# FY.net
KiCad netlist of a schematic drawn in EAGLE
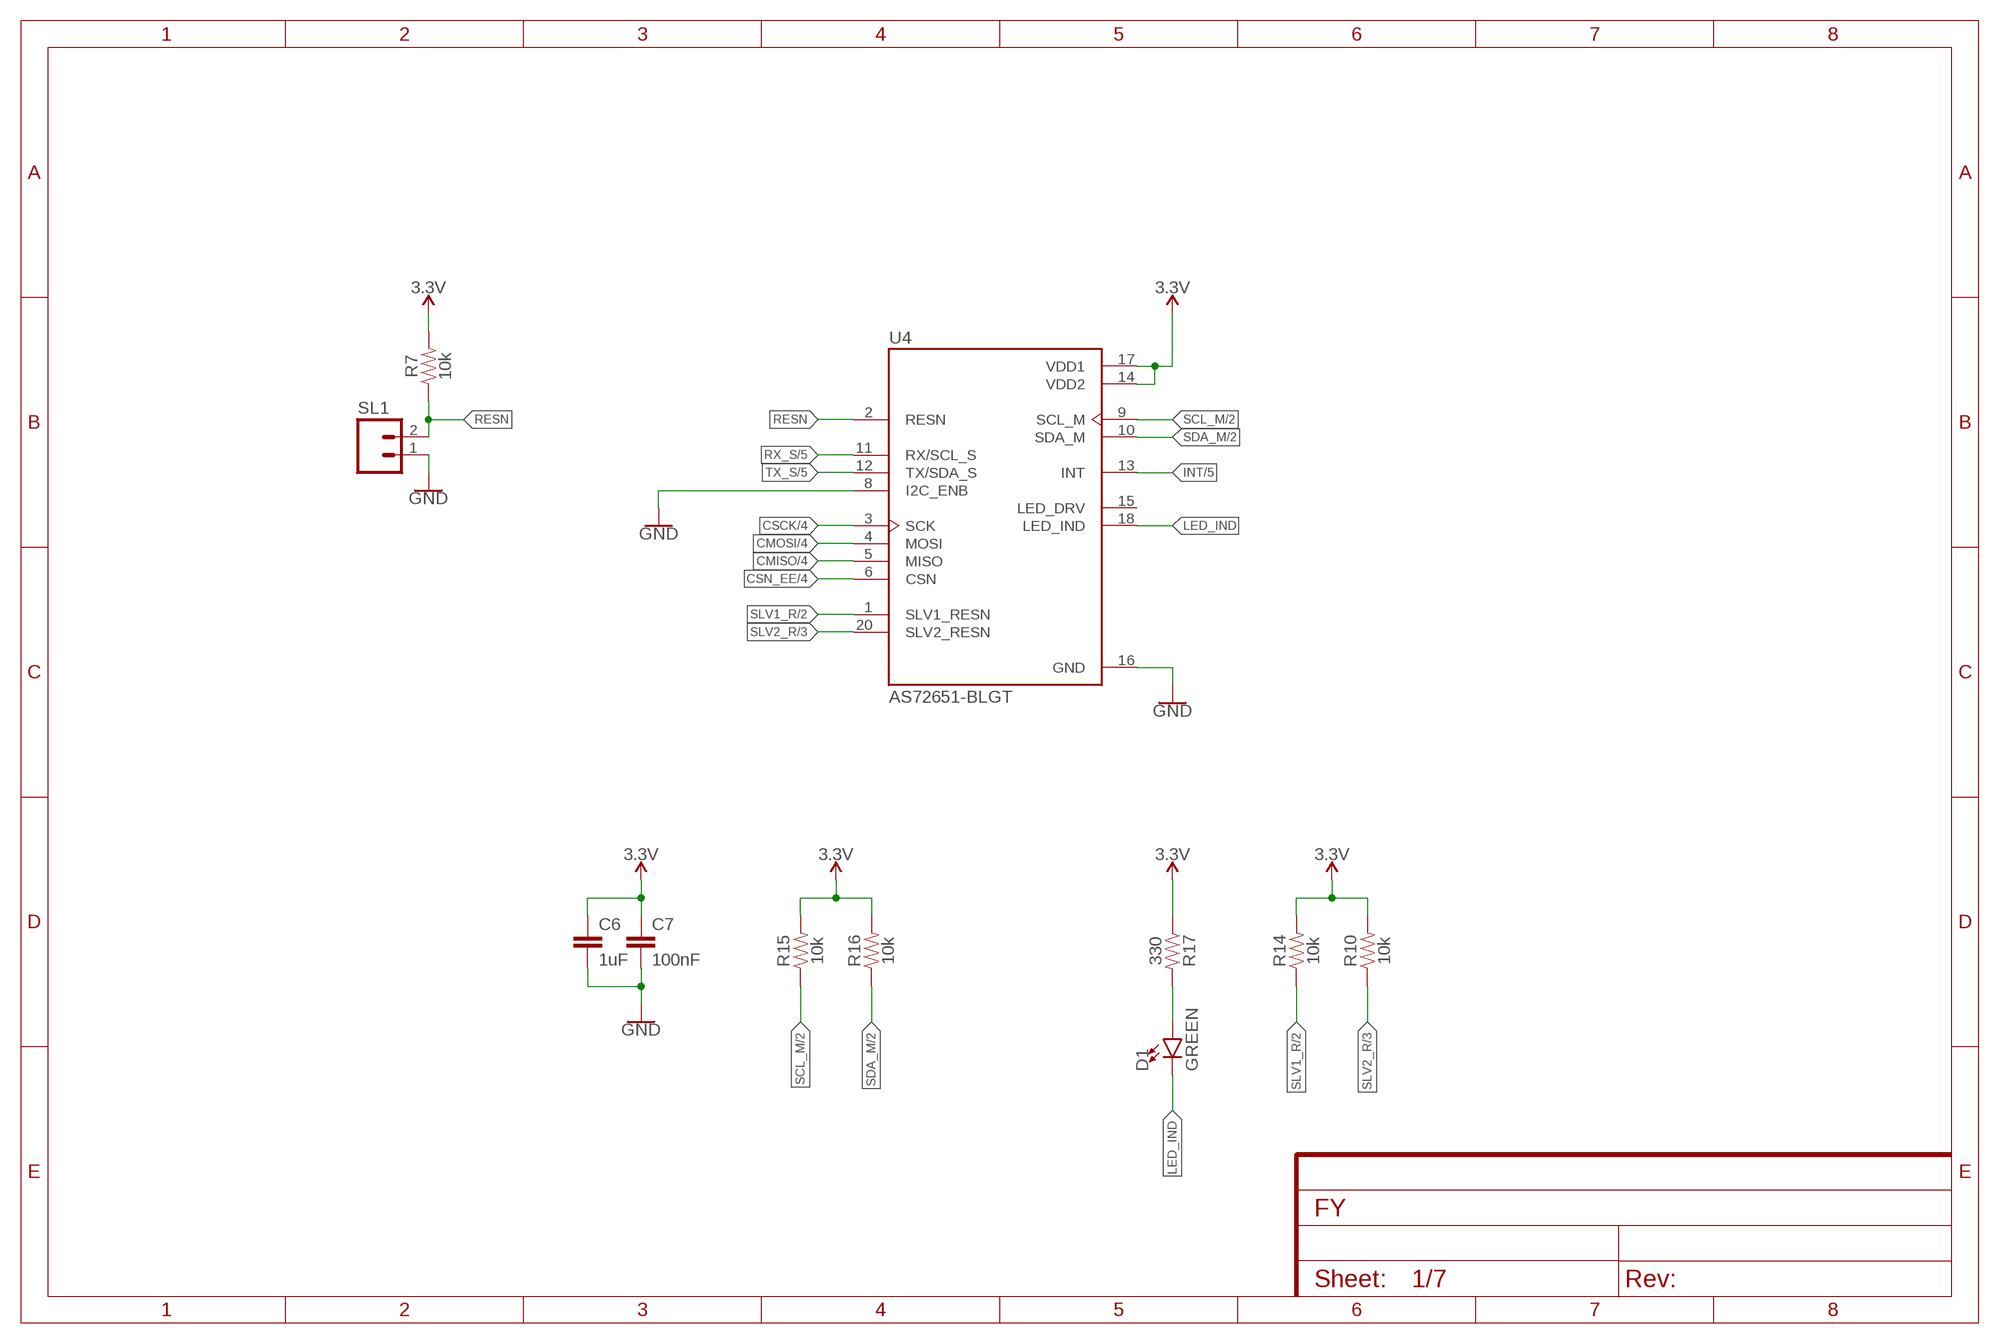
[diagram p0: schematic, sheet 1]
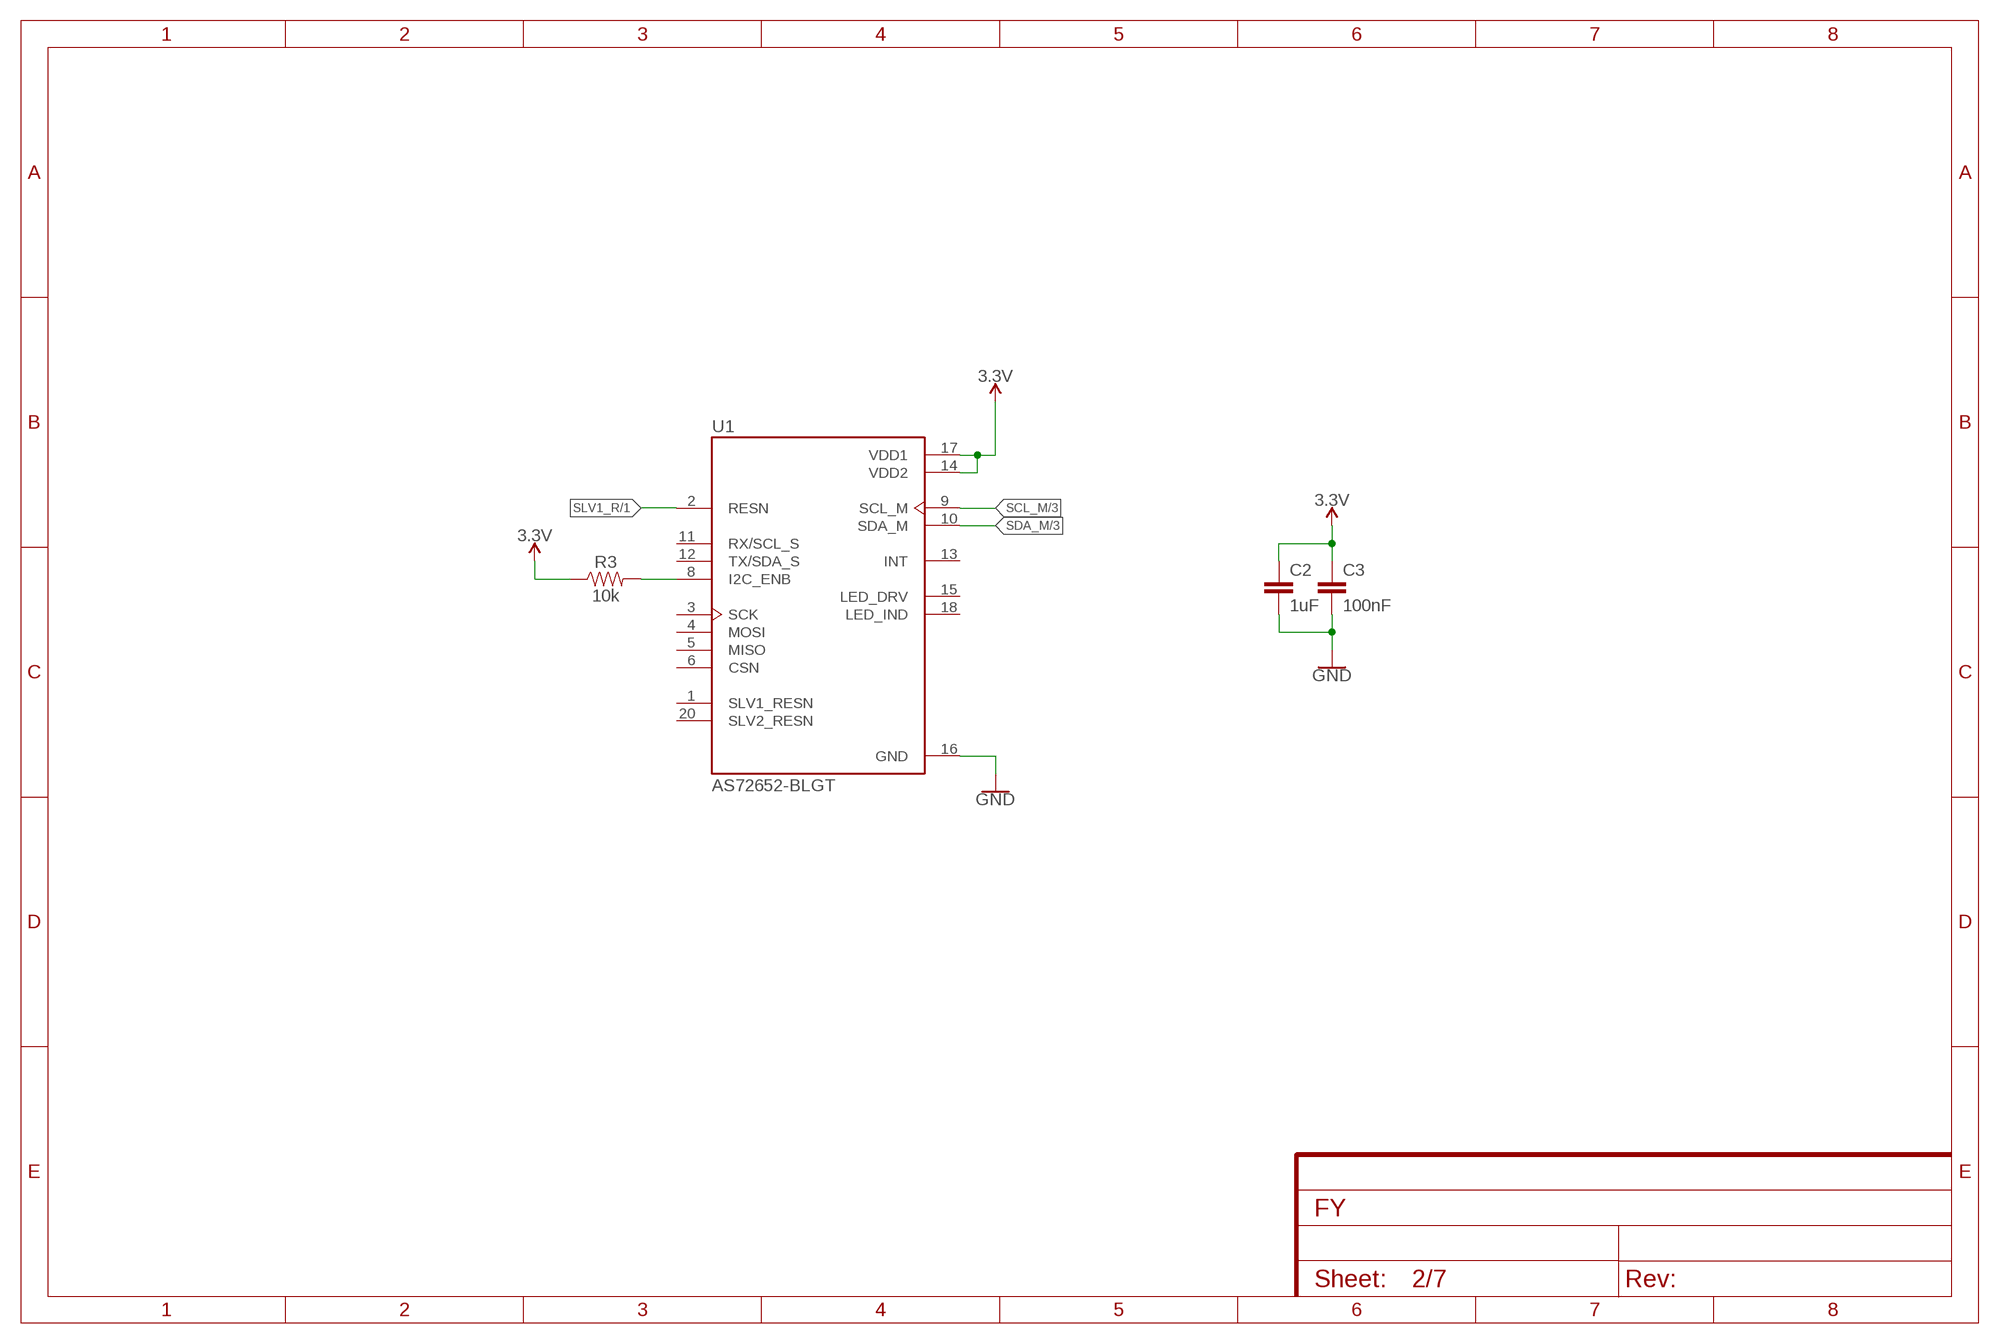
[diagram p1: schematic, sheet 2]
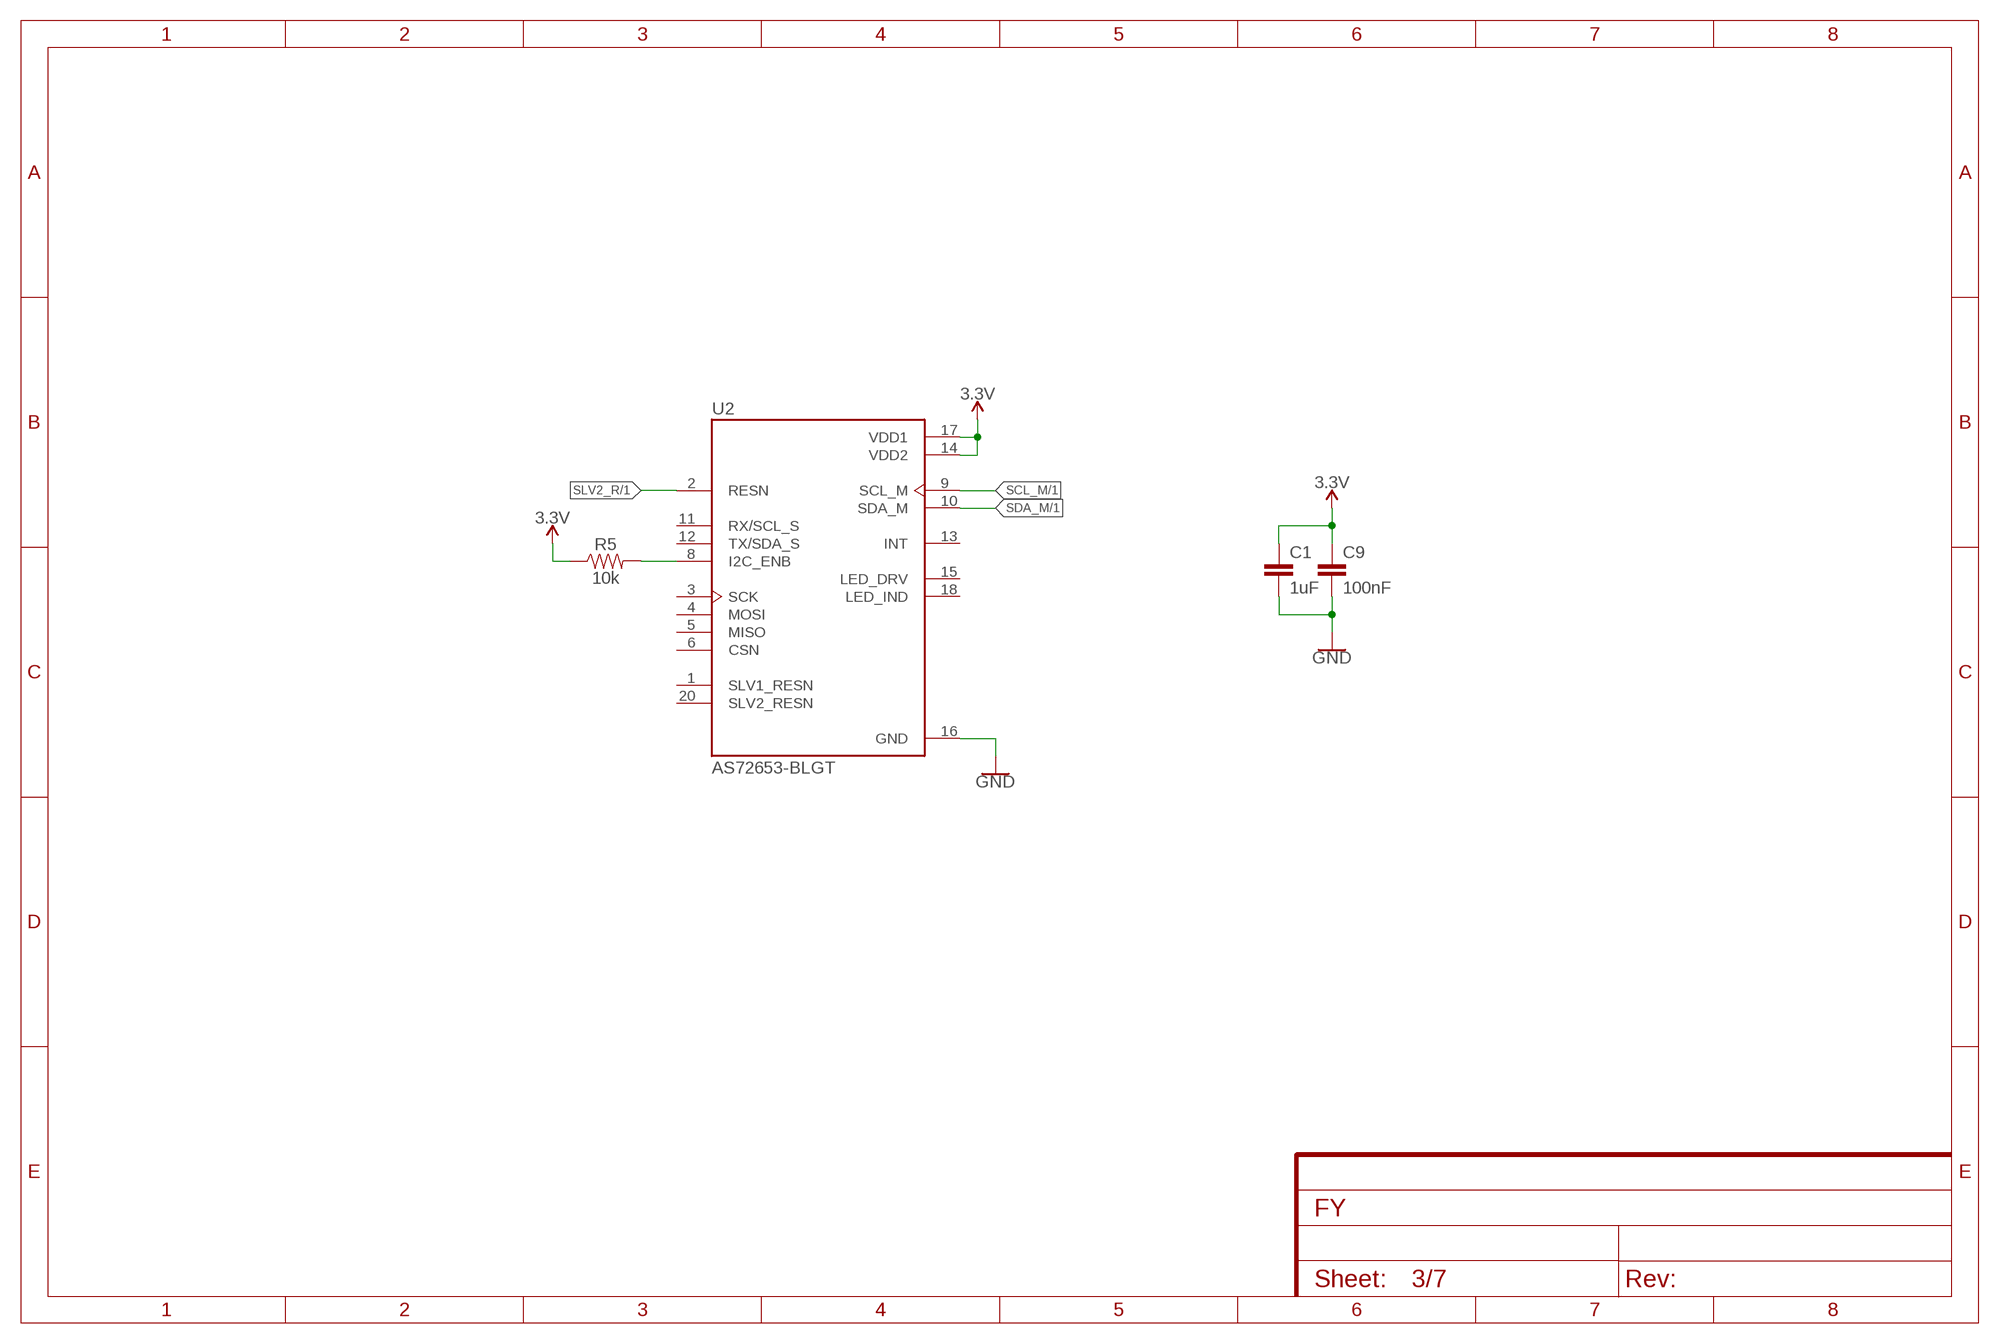
[diagram p2: schematic, sheet 3]
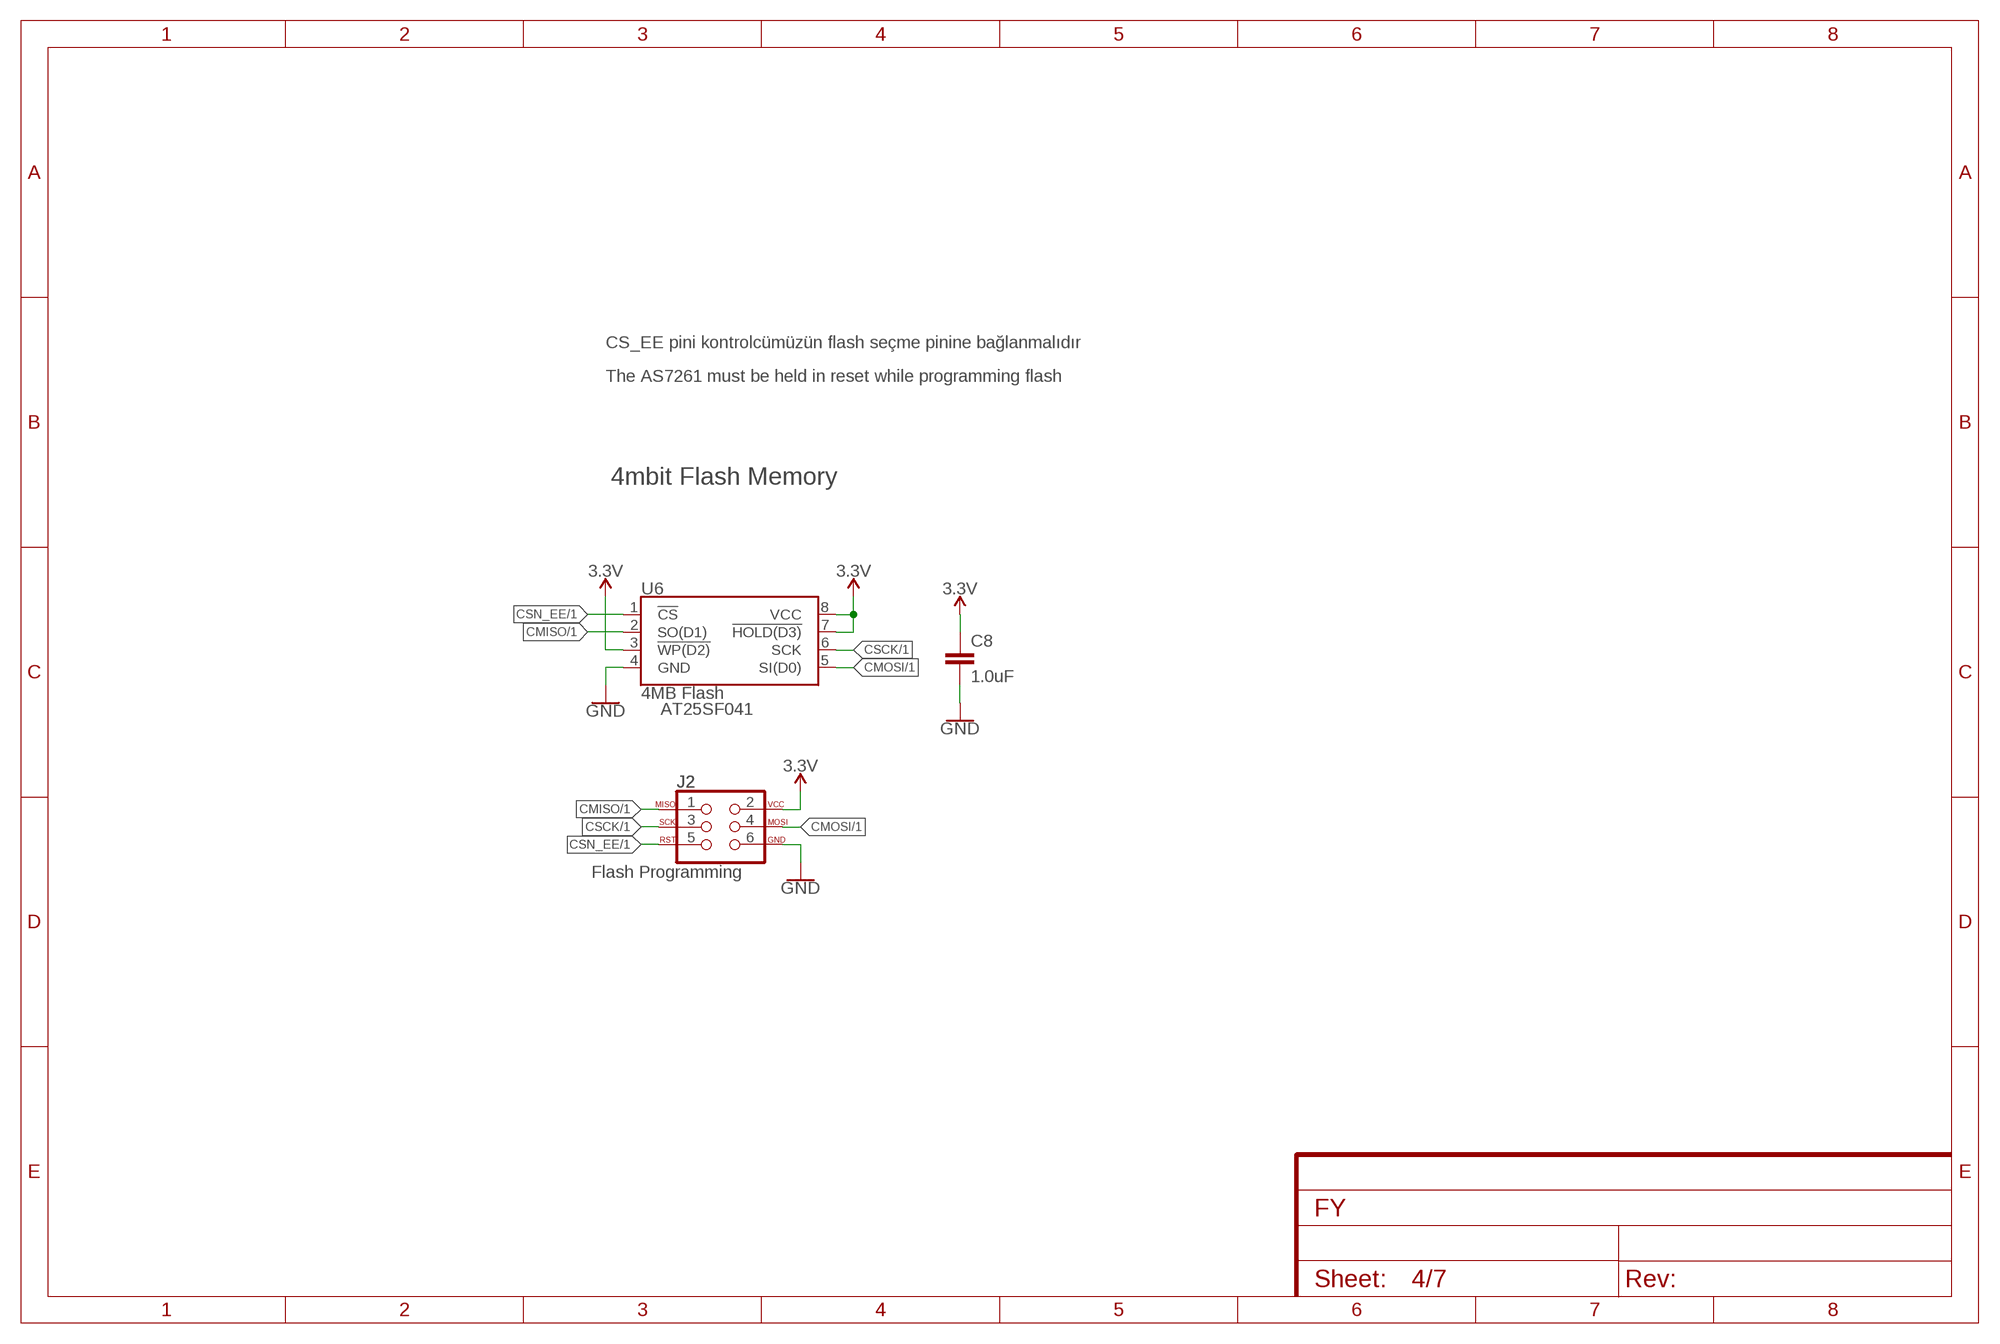
[diagram p3: schematic, sheet 4]
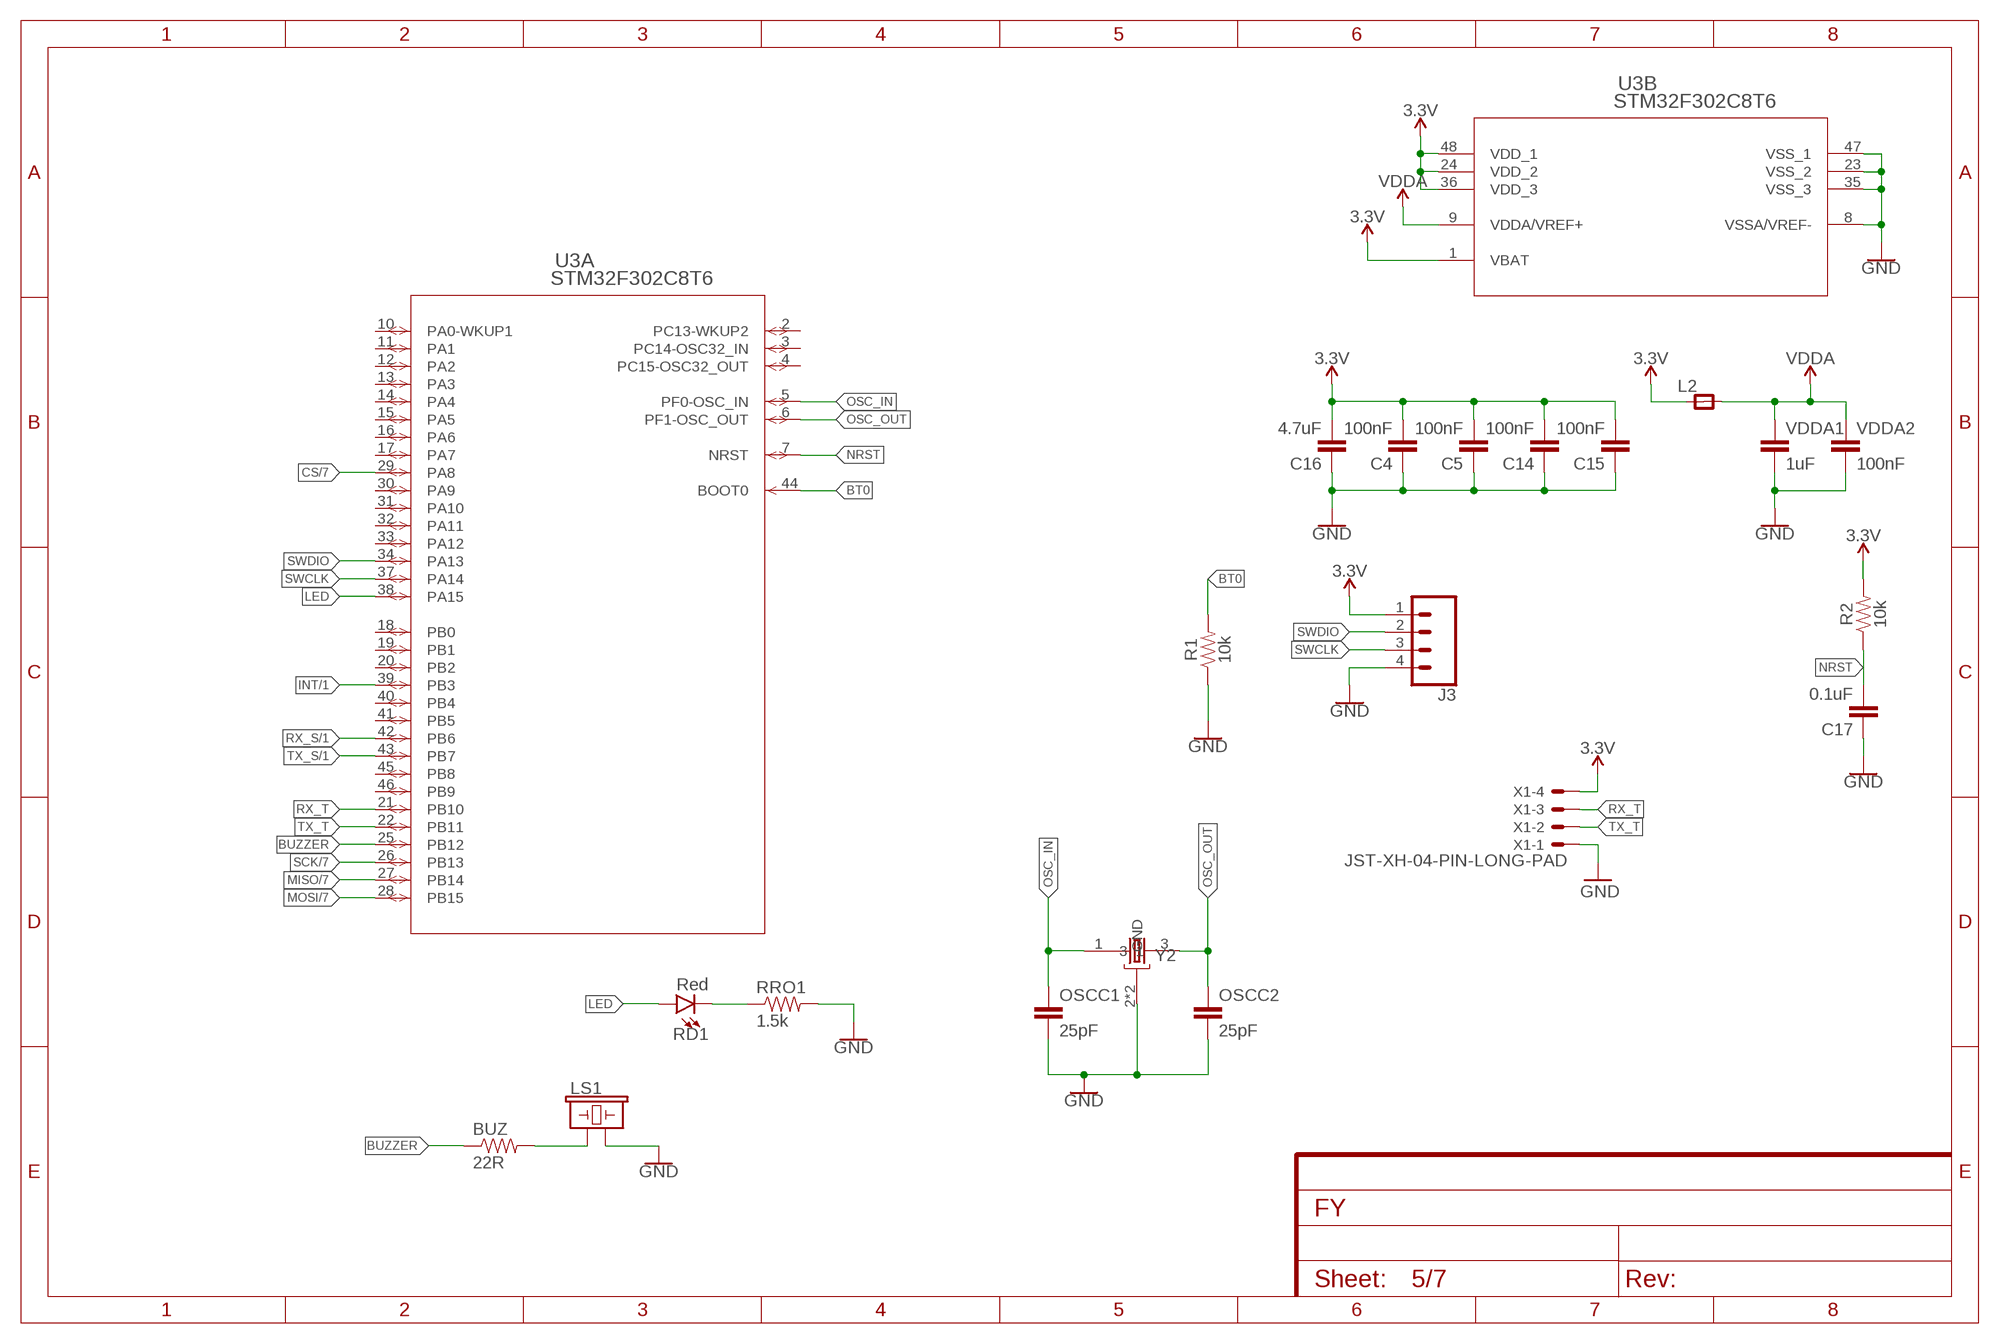
[diagram p4: schematic, sheet 5]
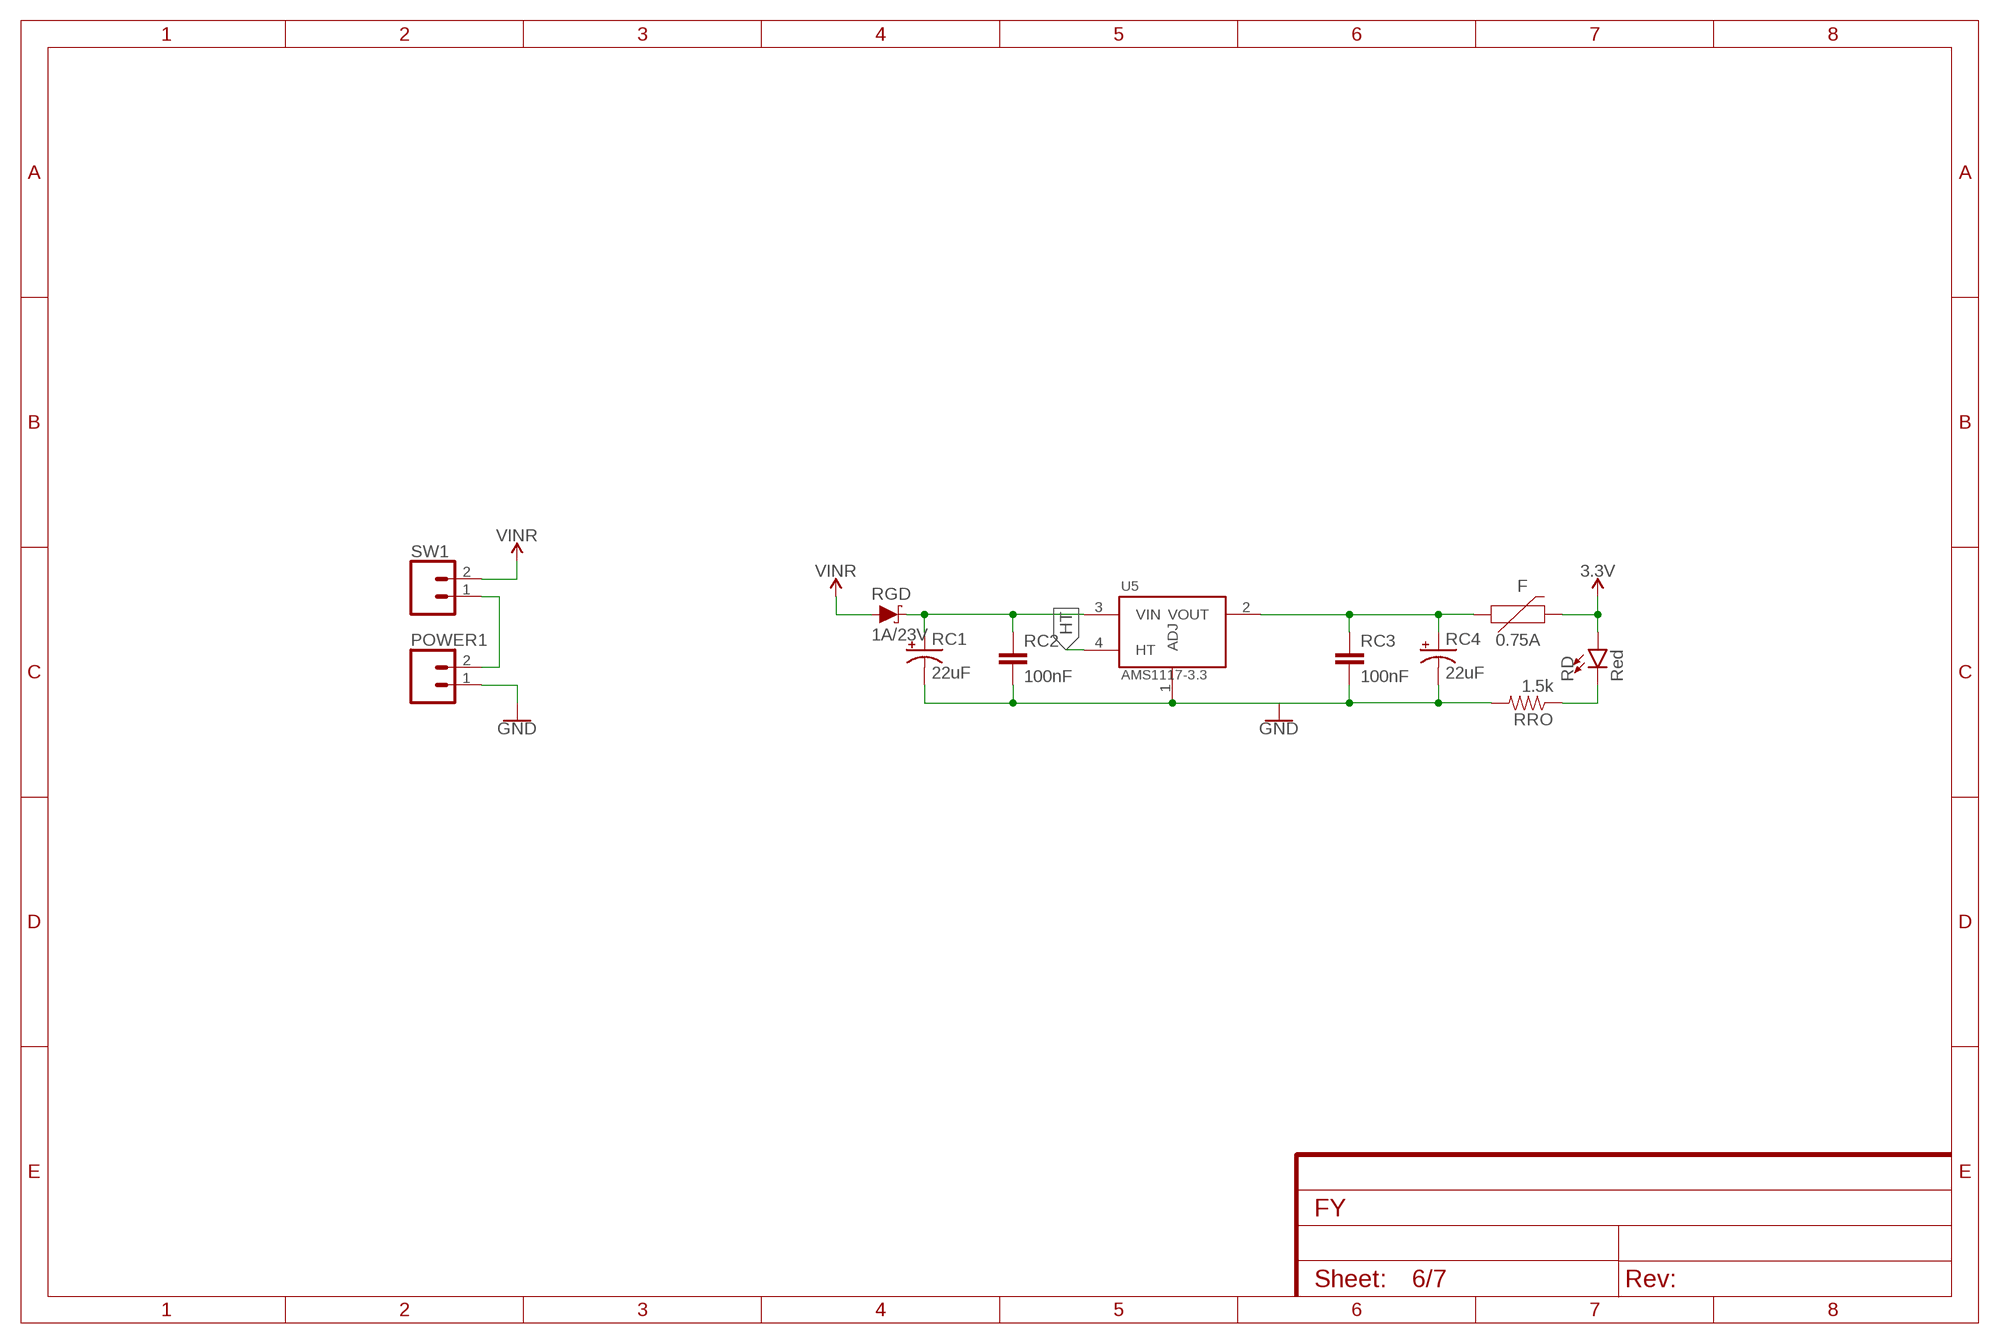
[diagram p5: schematic, sheet 6]
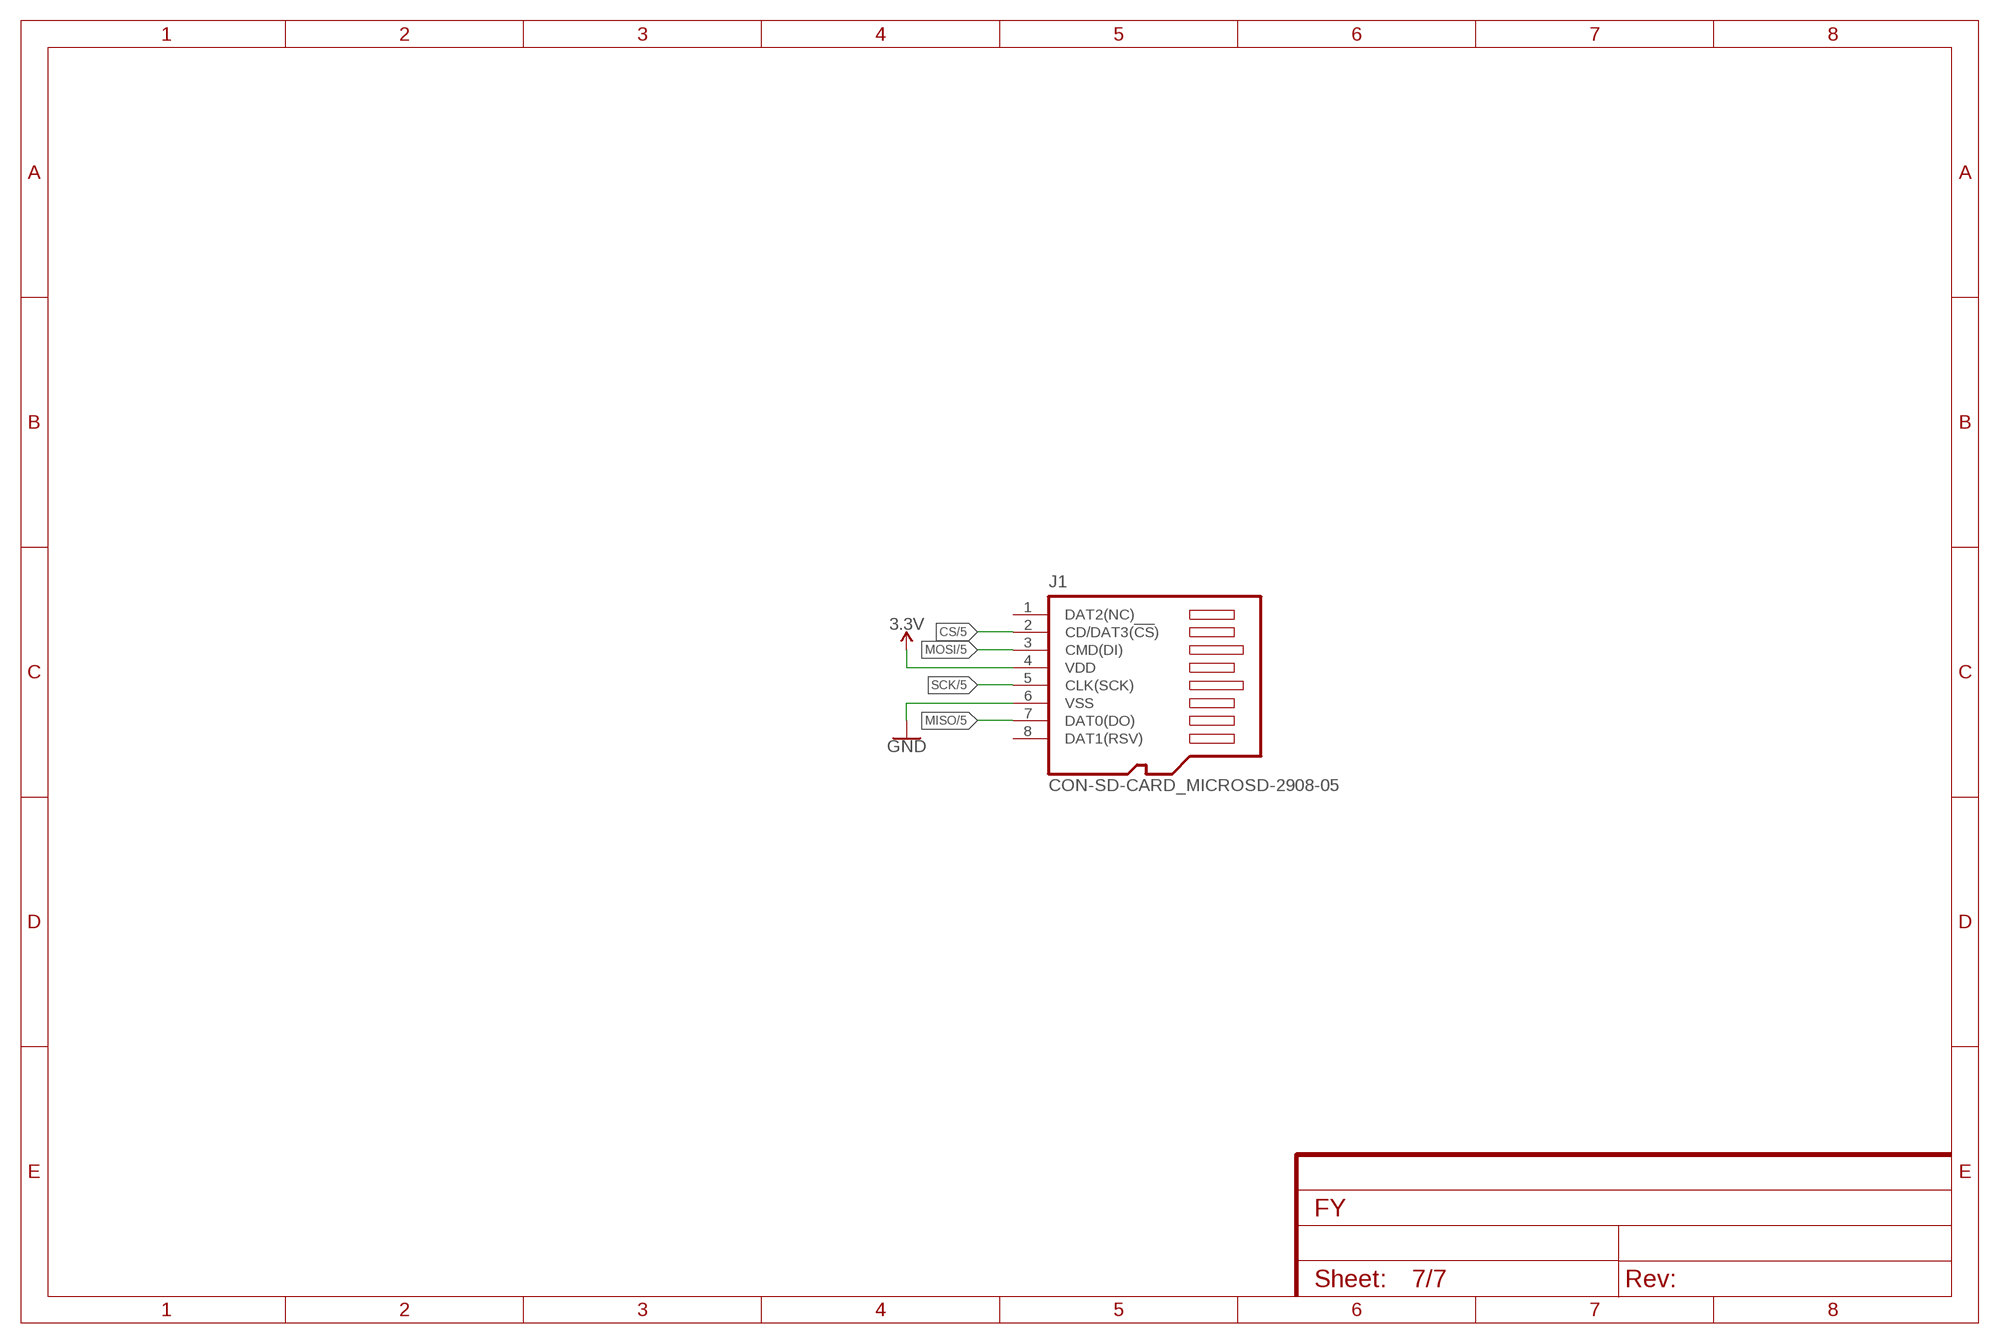
[diagram p6: schematic, sheet 7]

(export (version "E")
  (design (tool "Eeschema 10.0.6"))
  (components
    (comp (ref "C1")
      (value "1uF")
      (footprint "eagle-import:0603")
      (libsource (lib "eagle-import") (part "10UF-0603-6.3V-20%"))
    )
    (comp (ref "C9")
      (value "100nF")
      (footprint "eagle-import:0603")
      (libsource (lib "eagle-import") (part "0.1UF-0603-25V-(+80/-20%)"))
    )
    (comp (ref "R5")
      (value "10k")
      (footprint "eagle-import:0603")
      (libsource (lib "eagle-import") (part "0.05OHM-0603-1/5W-1%"))
    )
    (comp (ref "U2")
      (value "AS72653-BLGT")
      (footprint "eagle-import:PQFN65P470X450X270-20N")
      (fields (field (name "MF") "ams") (field (name "MP") "AS72651-BLGT"))
      (libsource (lib "eagle-import") (part "AS72651-BLGT"))
    )
    (comp (ref "C2")
      (value "1uF")
      (footprint "eagle-import:0603")
      (libsource (lib "eagle-import") (part "10UF-0603-6.3V-20%"))
    )
    (comp (ref "C3")
      (value "100nF")
      (footprint "eagle-import:0603")
      (libsource (lib "eagle-import") (part "0.1UF-0603-25V-(+80/-20%)"))
    )
    (comp (ref "R3")
      (value "10k")
      (footprint "eagle-import:0603")
      (libsource (lib "eagle-import") (part "0.05OHM-0603-1/5W-1%"))
    )
    (comp (ref "U1")
      (value "AS72652-BLGT")
      (footprint "eagle-import:PQFN65P470X450X270-20N")
      (fields (field (name "MF") "ams") (field (name "MP") "AS72651-BLGT"))
      (libsource (lib "eagle-import") (part "AS72651-BLGT"))
    )
    (comp (ref "C6")
      (value "1uF")
      (footprint "eagle-import:0603")
      (libsource (lib "eagle-import") (part "10UF-0603-6.3V-20%"))
    )
    (comp (ref "C7")
      (value "100nF")
      (footprint "eagle-import:0603")
      (libsource (lib "eagle-import") (part "0.1UF-0603-25V-(+80/-20%)"))
    )
    (comp (ref "D1")
      (value "GREEN")
      (footprint "eagle-import:LED-0603")
      (libsource (lib "eagle-import") (part "LED-GREEN0603"))
    )
    (comp (ref "R7")
      (value "10k")
      (footprint "eagle-import:0603")
      (libsource (lib "eagle-import") (part "10KOHM-0603-1/10W-1%"))
    )
    (comp (ref "R10")
      (value "10k")
      (footprint "eagle-import:0603")
      (libsource (lib "eagle-import") (part "10KOHM-0603-1/10W-1%"))
    )
    (comp (ref "R14")
      (value "10k")
      (footprint "eagle-import:0603")
      (libsource (lib "eagle-import") (part "10KOHM-0603-1/10W-1%"))
    )
    (comp (ref "R15")
      (value "10k")
      (footprint "eagle-import:0603")
      (libsource (lib "eagle-import") (part "10KOHM-0603-1/10W-1%"))
    )
    (comp (ref "R16")
      (value "10k")
      (footprint "eagle-import:0603")
      (libsource (lib "eagle-import") (part "10KOHM-0603-1/10W-1%"))
    )
    (comp (ref "R17")
      (value "330")
      (footprint "eagle-import:0603")
      (libsource (lib "eagle-import") (part "10KOHM-0603-1/10W-1%"))
    )
    (comp (ref "SL1")
      (value "M02")
      (footprint "eagle-import:02P")
      (libsource (lib "eagle-import") (part "M02"))
    )
    (comp (ref "U4")
      (value "AS72651-BLGT")
      (footprint "eagle-import:PQFN65P470X450X270-20N")
      (fields (field (name "MF") "ams"))
      (libsource (lib "eagle-import") (part "AS72651-BLGT"))
    )
    (comp (ref "J1")
      (value "CON-SD-CARD_MICROSD-2908-05")
      (footprint "eagle-import:CON-SD-CARD_2908-05")
      (libsource (lib "eagle-import") (part "CON-SD-CARD_MICROSD-2908-05"))
    )
    (comp (ref "C8")
      (value "1.0uF")
      (footprint "eagle-import:0603")
      (libsource (lib "eagle-import") (part "1.0UF-0603-16V-10%"))
    )
    (comp (ref "J2")
      (value "Flash Programming")
      (footprint "eagle-import:2X3_TEST_POINTS")
      (libsource (lib "eagle-import") (part "AVR_SPI_PROG_3X2TESTPOINTS"))
    )
    (comp (ref "U6")
      (value "4MB Flash")
      (footprint "eagle-import:SO08")
      (libsource (lib "eagle-import") (part "AT25SF041"))
    )
    (comp (ref "BUZ")
      (value "22R")
      (footprint "eagle-import:0603-RES")
      (libsource (lib "eagle-import") (part "2.0KOHM1/10W5%(0603)"))
    )
    (comp (ref "C4")
      (value "100nF")
      (footprint "eagle-import:0603")
      (libsource (lib "eagle-import") (part "22PF-0603-50V-5%"))
    )
    (comp (ref "C5")
      (value "100nF")
      (footprint "eagle-import:0603")
      (libsource (lib "eagle-import") (part "22PF-0603-50V-5%"))
    )
    (comp (ref "C14")
      (value "100nF")
      (footprint "eagle-import:0603")
      (libsource (lib "eagle-import") (part "22PF-0603-50V-5%"))
    )
    (comp (ref "C15")
      (value "100nF")
      (footprint "eagle-import:0603")
      (libsource (lib "eagle-import") (part "22PF-0603-50V-5%"))
    )
    (comp (ref "C16")
      (value "4.7uF")
      (footprint "eagle-import:0603")
      (libsource (lib "eagle-import") (part "22PF-0603-50V-5%"))
    )
    (comp (ref "C17")
      (value "0.1uF")
      (footprint "eagle-import:0603")
      (libsource (lib "eagle-import") (part "22PF-0603-50V-5%"))
    )
    (comp (ref "J3")
      (value "CONN_04")
      (footprint "eagle-import:1X04")
      (libsource (lib "eagle-import") (part "CONN_04"))
    )
    (comp (ref "L2")
      (value "RC-MASTER-SMD_FB_0805MP")
      (footprint "eagle-import:RC-MASTER-SMD_L0805MP")
      (libsource (lib "eagle-import") (part "RC-MASTER-SMD_FB_0805MP"))
    )
    (comp (ref "LS1")
      (value "BUZZER-PTH")
      (footprint "eagle-import:BUZZER-12MM")
      (libsource (lib "eagle-import") (part "BUZZER-PTH"))
    )
    (comp (ref "OSCC1")
      (value "25pF")
      (footprint "eagle-import:0603")
      (libsource (lib "eagle-import") (part "SparkFun-Capacitors_510_0.1UF-0603-25V-(+80/-20%)"))
    )
    (comp (ref "OSCC2")
      (value "25pF")
      (footprint "eagle-import:0603")
      (libsource (lib "eagle-import") (part "SparkFun-Capacitors_510_0.1UF-0603-25V-(+80/-20%)"))
    )
    (comp (ref "R1")
      (value "10k")
      (footprint "eagle-import:0603")
      (libsource (lib "eagle-import") (part "0.05OHM-0603-1/5W-1%"))
    )
    (comp (ref "R2")
      (value "10k")
      (footprint "eagle-import:0603")
      (libsource (lib "eagle-import") (part "0.05OHM-0603-1/5W-1%"))
    )
    (comp (ref "RD1")
      (value "Red")
      (footprint "eagle-import:LED-0603")
      (libsource (lib "eagle-import") (part "LED-RED0603-SMART"))
    )
    (comp (ref "RRO1")
      (value "1.5k")
      (footprint "eagle-import:0603-RES")
      (libsource (lib "eagle-import") (part "2.0KOHM1/10W5%(0603)"))
    )
    (comp (ref "U3")
      (value "STM32F302C8T6")
      (footprint "eagle-import:LQFP48-7X7MM")
      (fields (field (name "COPYRIGHT") "Copyright (C) 2018 Accelerated Designs. All rights reserved"))
      (libsource (lib "eagle-import") (part "STM32F302C8T6"))
    )
    (comp (ref "VDDA1")
      (value "1uF")
      (footprint "eagle-import:0603")
      (libsource (lib "eagle-import") (part "SparkFun-Capacitors_510_0.1UF-0603-25V-(+80/-20%)"))
    )
    (comp (ref "VDDA2")
      (value "100nF")
      (footprint "eagle-import:0603")
      (libsource (lib "eagle-import") (part "SparkFun-Capacitors_510_0.1UF-0603-25V-(+80/-20%)"))
    )
    (comp (ref "X1")
      (value "JST-XH-04-PIN-LONG-PAD")
      (footprint "eagle-import:JST-XH-04-PACKAGE-LONG-PAD")
      (libsource (lib "eagle-import") (part "JST-XH-04-PIN-LONG-PAD"))
    )
    (comp (ref "Y2")
      (value "ABM2B-8.000MHZ-10-1-U-T")
      (footprint "eagle-import:OSCCC500X320X110-4N")
      (fields (field (name "MF") "Abracon") (field (name "MP") "ABM3B-26.000MHZ-10-1-U-T"))
      (libsource (lib "eagle-import") (part "ABM3B-26.000MHZ-10-1-U-T"))
    )
    (comp (ref "F")
      (value "0.75A")
      (footprint "eagle-import:1206")
      (libsource (lib "eagle-import") (part "PPTC_THREE-QUARTER-AMP"))
    )
    (comp (ref "POWER1")
      (value "CONN_023.5MM-NO_SILK")
      (footprint "eagle-import:SCREWTERMINAL-3.5MM-2-NS")
      (libsource (lib "eagle-import") (part "CONN_023.5MM-NO_SILK"))
    )
    (comp (ref "RC1")
      (value "22uF")
      (footprint "eagle-import:EIA3528")
      (libsource (lib "eagle-import") (part "10UF-POLAR-EIA3528-20V-10%(TANT)"))
    )
    (comp (ref "RC2")
      (value "100nF")
      (footprint "eagle-import:0603")
      (libsource (lib "eagle-import") (part "SparkFun-Capacitors_510_0.1UF-0603-25V-(+80/-20%)"))
    )
    (comp (ref "RC3")
      (value "100nF")
      (footprint "eagle-import:0603")
      (libsource (lib "eagle-import") (part "SparkFun-Capacitors_510_0.1UF-0603-25V-(+80/-20%)"))
    )
    (comp (ref "RC4")
      (value "22uF")
      (footprint "eagle-import:EIA3528")
      (libsource (lib "eagle-import") (part "10UF-POLAR-EIA3528-20V-10%(TANT)"))
    )
    (comp (ref "RD")
      (value "Red")
      (footprint "eagle-import:LED-0603")
      (libsource (lib "eagle-import") (part "LED-RED0603-SMART"))
    )
    (comp (ref "RGD")
      (value "1A/23V")
      (footprint "eagle-import:SOD-323")
      (libsource (lib "eagle-import") (part "DIODE-SCHOTTKY-BAT20J"))
    )
    (comp (ref "RRO")
      (value "1.5k")
      (footprint "eagle-import:0603-RES")
      (libsource (lib "eagle-import") (part "2.0KOHM1/10W5%(0603)"))
    )
    (comp (ref "SW1")
      (value "CONN_023.5MM-NO_SILK")
      (footprint "eagle-import:SCREWTERMINAL-3.5MM-2-NS")
      (libsource (lib "eagle-import") (part "CONN_023.5MM-NO_SILK"))
    )
    (comp (ref "U5")
      (value "AMS1117-3.3")
      (footprint "eagle-import:SOT229P700X180-4N")
      (fields (field (name "MF") "Advanced Monolithic Systems"))
      (libsource (lib "eagle-import") (part "AMS1117-3.3"))
    )
  )
  (nets
    (net (code "1") (name "3.3V") (class "Default")
      (node (ref "C1") (pin "1") (pinfunction "1_1") (pintype "passive"))
      (node (ref "C14") (pin "2") (pinfunction "2_2") (pintype "passive"))
      (node (ref "C15") (pin "2") (pinfunction "2_2") (pintype "passive"))
      (node (ref "C16") (pin "2") (pinfunction "2_2") (pintype "passive"))
      (node (ref "C2") (pin "1") (pinfunction "1_1") (pintype "passive"))
      (node (ref "C3") (pin "1") (pinfunction "1_1") (pintype "passive"))
      (node (ref "C4") (pin "2") (pinfunction "2_2") (pintype "passive"))
      (node (ref "C5") (pin "2") (pinfunction "2_2") (pintype "passive"))
      (node (ref "C6") (pin "1") (pinfunction "1_1") (pintype "passive"))
      (node (ref "C7") (pin "1") (pinfunction "1_1") (pintype "passive"))
      (node (ref "C8") (pin "1") (pinfunction "1_1") (pintype "passive"))
      (node (ref "C9") (pin "1") (pinfunction "1_1") (pintype "passive"))
      (node (ref "F") (pin "2") (pinfunction "2_2") (pintype "bidirectional"))
      (node (ref "J1") (pin "4") (pinfunction "VDD_4") (pintype "bidirectional"))
      (node (ref "J2") (pin "2") (pinfunction "2_2") (pintype "passive"))
      (node (ref "J3") (pin "1") (pinfunction "1_1") (pintype "passive"))
      (node (ref "L2") (pin "1") (pinfunction "1_1") (pintype "passive"))
      (node (ref "R10") (pin "2") (pinfunction "2_2") (pintype "passive"))
      (node (ref "R14") (pin "2") (pinfunction "2_2") (pintype "passive"))
      (node (ref "R15") (pin "2") (pinfunction "2_2") (pintype "passive"))
      (node (ref "R16") (pin "2") (pinfunction "2_2") (pintype "passive"))
      (node (ref "R17") (pin "1") (pinfunction "1_1") (pintype "passive"))
      (node (ref "R2") (pin "2") (pinfunction "2_2") (pintype "passive"))
      (node (ref "R3") (pin "1") (pinfunction "1_1") (pintype "passive"))
      (node (ref "R5") (pin "1") (pinfunction "1_1") (pintype "passive"))
      (node (ref "R7") (pin "2") (pinfunction "2_2") (pintype "passive"))
      (node (ref "RD") (pin "A") (pinfunction "A_A") (pintype "passive"))
      (node (ref "U1") (pin "14") (pinfunction "VDD2_14") (pintype "power_in"))
      (node (ref "U1") (pin "17") (pinfunction "VDD1_17") (pintype "power_in"))
      (node (ref "U2") (pin "14") (pinfunction "VDD2_14") (pintype "power_in"))
      (node (ref "U2") (pin "17") (pinfunction "VDD1_17") (pintype "power_in"))
      (node (ref "U3") (pin "1") (pinfunction "VBAT_1") (pintype "power_in"))
      (node (ref "U3") (pin "24") (pinfunction "VDD_2_24") (pintype "power_in"))
      (node (ref "U3") (pin "36") (pinfunction "VDD_3_36") (pintype "power_in"))
      (node (ref "U3") (pin "48") (pinfunction "VDD_1_48") (pintype "power_in"))
      (node (ref "U4") (pin "14") (pinfunction "VDD2_14") (pintype "power_in"))
      (node (ref "U4") (pin "17") (pinfunction "VDD1_17") (pintype "power_in"))
      (node (ref "U6") (pin "3") (pinfunction "~{WP(D2})_3") (pintype "bidirectional"))
      (node (ref "U6") (pin "7") (pinfunction "~{HOLD(D3})_7") (pintype "bidirectional"))
      (node (ref "U6") (pin "8") (pinfunction "VCC_8") (pintype "bidirectional"))
      (node (ref "X1") (pin "4") (pinfunction "S_4") (pintype "passive"))
    )
    (net (code "2") (name "BT0") (class "Default")
      (node (ref "R1") (pin "2") (pinfunction "2_2") (pintype "passive"))
      (node (ref "U3") (pin "44") (pinfunction "BOOT0_44") (pintype "input"))
    )
    (net (code "3") (name "BUZZER") (class "Default")
      (node (ref "BUZ") (pin "1") (pinfunction "1_1") (pintype "passive"))
      (node (ref "U3") (pin "25") (pinfunction "PB12_25") (pintype "bidirectional"))
    )
    (net (code "4") (name "CMISO") (class "Default")
      (node (ref "J2") (pin "1") (pinfunction "1_1") (pintype "passive"))
      (node (ref "U4") (pin "5") (pinfunction "MISO_5") (pintype "bidirectional"))
      (node (ref "U6") (pin "2") (pinfunction "SO(D1)_2") (pintype "bidirectional"))
    )
    (net (code "5") (name "CMOSI") (class "Default")
      (node (ref "J2") (pin "4") (pinfunction "4_4") (pintype "passive"))
      (node (ref "U4") (pin "4") (pinfunction "MOSI_4") (pintype "bidirectional"))
      (node (ref "U6") (pin "5") (pinfunction "SI(D0)_5") (pintype "bidirectional"))
    )
    (net (code "6") (name "CS") (class "Default")
      (node (ref "J1") (pin "2") (pinfunction "CD/DAT3(~{CS})_2") (pintype "bidirectional"))
      (node (ref "U3") (pin "29") (pinfunction "PA8_29") (pintype "bidirectional"))
    )
    (net (code "7") (name "CSCK") (class "Default")
      (node (ref "J2") (pin "3") (pinfunction "3_3") (pintype "passive"))
      (node (ref "U4") (pin "3") (pinfunction "SCK_3") (pintype "output"))
      (node (ref "U6") (pin "6") (pinfunction "SCK_6") (pintype "bidirectional"))
    )
    (net (code "8") (name "CSN_EE") (class "Default")
      (node (ref "J2") (pin "5") (pinfunction "5_5") (pintype "passive"))
      (node (ref "U4") (pin "6") (pinfunction "CSN_6") (pintype "output"))
      (node (ref "U6") (pin "1") (pinfunction "~{CS}_1") (pintype "bidirectional"))
    )
    (net (code "9") (name "GND") (class "Default")
      (node (ref "C1") (pin "2") (pinfunction "2_2") (pintype "passive"))
      (node (ref "C14") (pin "1") (pinfunction "1_1") (pintype "passive"))
      (node (ref "C15") (pin "1") (pinfunction "1_1") (pintype "passive"))
      (node (ref "C16") (pin "1") (pinfunction "1_1") (pintype "passive"))
      (node (ref "C17") (pin "1") (pinfunction "1_1") (pintype "passive"))
      (node (ref "C2") (pin "2") (pinfunction "2_2") (pintype "passive"))
      (node (ref "C3") (pin "2") (pinfunction "2_2") (pintype "passive"))
      (node (ref "C4") (pin "1") (pinfunction "1_1") (pintype "passive"))
      (node (ref "C5") (pin "1") (pinfunction "1_1") (pintype "passive"))
      (node (ref "C6") (pin "2") (pinfunction "2_2") (pintype "passive"))
      (node (ref "C7") (pin "2") (pinfunction "2_2") (pintype "passive"))
      (node (ref "C8") (pin "2") (pinfunction "2_2") (pintype "passive"))
      (node (ref "C9") (pin "2") (pinfunction "2_2") (pintype "passive"))
      (node (ref "J1") (pin "6") (pinfunction "VSS_6") (pintype "bidirectional"))
      (node (ref "J2") (pin "6") (pinfunction "6_6") (pintype "passive"))
      (node (ref "J3") (pin "4") (pinfunction "4_4") (pintype "passive"))
      (node (ref "LS1") (pin "-") (pinfunction "2_-") (pintype "passive"))
      (node (ref "OSCC1") (pin "2") (pinfunction "2_2") (pintype "passive"))
      (node (ref "OSCC2") (pin "2") (pinfunction "2_2") (pintype "passive"))
      (node (ref "POWER1") (pin "1") (pinfunction "1_1") (pintype "passive"))
      (node (ref "R1") (pin "1") (pinfunction "1_1") (pintype "passive"))
      (node (ref "RC1") (pin "C") (pinfunction "-_C") (pintype "passive"))
      (node (ref "RC2") (pin "2") (pinfunction "2_2") (pintype "passive"))
      (node (ref "RC3") (pin "2") (pinfunction "2_2") (pintype "passive"))
      (node (ref "RC4") (pin "C") (pinfunction "-_C") (pintype "passive"))
      (node (ref "RRO") (pin "2") (pinfunction "2_2") (pintype "passive"))
      (node (ref "RRO1") (pin "2") (pinfunction "2_2") (pintype "passive"))
      (node (ref "SL1") (pin "1") (pinfunction "1_1") (pintype "passive"))
      (node (ref "U1") (pin "16") (pinfunction "GND_16") (pintype "power_in"))
      (node (ref "U2") (pin "16") (pinfunction "GND_16") (pintype "power_in"))
      (node (ref "U3") (pin "23") (pinfunction "VSS_2_23") (pintype "power_in"))
      (node (ref "U3") (pin "35") (pinfunction "VSS_3_35") (pintype "power_in"))
      (node (ref "U3") (pin "47") (pinfunction "VSS_1_47") (pintype "power_in"))
      (node (ref "U3") (pin "8") (pinfunction "VSSA/VREF-_8") (pintype "power_in"))
      (node (ref "U4") (pin "16") (pinfunction "GND_16") (pintype "power_in"))
      (node (ref "U4") (pin "8") (pinfunction "I2C_ENB_8") (pintype "input"))
      (node (ref "U5") (pin "1") (pinfunction "ADJ_1") (pintype "power_in"))
      (node (ref "U6") (pin "4") (pinfunction "GND_4") (pintype "bidirectional"))
      (node (ref "VDDA1") (pin "2") (pinfunction "2_2") (pintype "passive"))
      (node (ref "VDDA2") (pin "2") (pinfunction "2_2") (pintype "passive"))
      (node (ref "X1") (pin "1") (pinfunction "S_1") (pintype "passive"))
      (node (ref "Y2") (pin "2") (pinfunction "GND_2") (pintype "passive"))
      (node (ref "Y2") (pin "4") (pinfunction "GND_4") (pintype "passive"))
    )
    (net (code "10") (name "HT") (class "Default")
      (node (ref "U5") (pin "4") (pinfunction "HT_4") (pintype "bidirectional"))
    )
    (net (code "11") (name "INT") (class "Default")
      (node (ref "U3") (pin "39") (pinfunction "PB3_39") (pintype "bidirectional"))
      (node (ref "U4") (pin "13") (pinfunction "INT_13") (pintype "output"))
    )
    (net (code "12") (name "LED") (class "Default")
      (node (ref "RD1") (pin "A") (pinfunction "A_A") (pintype "passive"))
      (node (ref "U3") (pin "38") (pinfunction "PA15_38") (pintype "bidirectional"))
    )
    (net (code "13") (name "LED_IND") (class "Default")
      (node (ref "D1") (pin "C") (pinfunction "C_C") (pintype "passive"))
      (node (ref "U4") (pin "18") (pinfunction "LED_IND_18") (pintype "output"))
    )
    (net (code "14") (name "MISO") (class "Default")
      (node (ref "J1") (pin "7") (pinfunction "DAT0(DO)_7") (pintype "bidirectional"))
      (node (ref "U3") (pin "27") (pinfunction "PB14_27") (pintype "bidirectional"))
    )
    (net (code "15") (name "MOSI") (class "Default")
      (node (ref "J1") (pin "3") (pinfunction "CMD(DI)_3") (pintype "bidirectional"))
      (node (ref "U3") (pin "28") (pinfunction "PB15_28") (pintype "bidirectional"))
    )
    (net (code "16") (name "NRST") (class "Default")
      (node (ref "C17") (pin "2") (pinfunction "2_2") (pintype "passive"))
      (node (ref "R2") (pin "1") (pinfunction "1_1") (pintype "passive"))
      (node (ref "U3") (pin "7") (pinfunction "NRST_7") (pintype "bidirectional"))
    )
    (net (code "17") (name "Net-(D1-PadA)") (class "Default")
      (node (ref "D1") (pin "A") (pinfunction "A_A") (pintype "passive"))
      (node (ref "R17") (pin "2") (pinfunction "2_2") (pintype "passive"))
    )
    (net (code "18") (name "Net-(LS1-1)") (class "Default")
      (node (ref "BUZ") (pin "2") (pinfunction "2_2") (pintype "passive"))
      (node (ref "LS1") (pin "+") (pinfunction "1_+") (pintype "passive"))
    )
    (net (code "19") (name "Net-(POWER1-Pad2)") (class "Default")
      (node (ref "POWER1") (pin "2") (pinfunction "2_2") (pintype "passive"))
      (node (ref "SW1") (pin "1") (pinfunction "1_1") (pintype "passive"))
    )
    (net (code "20") (name "Net-(RC1-+)") (class "Default")
      (node (ref "RC1") (pin "A") (pinfunction "+_A") (pintype "passive"))
      (node (ref "RC2") (pin "1") (pinfunction "1_1") (pintype "passive"))
      (node (ref "RGD") (pin "C") (pinfunction "C_C") (pintype "passive"))
      (node (ref "U5") (pin "3") (pinfunction "VIN_3") (pintype "input"))
    )
    (net (code "21") (name "Net-(RC4-+)") (class "Default")
      (node (ref "F") (pin "1") (pinfunction "1_1") (pintype "bidirectional"))
      (node (ref "RC3") (pin "1") (pinfunction "1_1") (pintype "passive"))
      (node (ref "RC4") (pin "A") (pinfunction "+_A") (pintype "passive"))
      (node (ref "U5") (pin "2") (pinfunction "VOUT_2") (pintype "output"))
    )
    (net (code "22") (name "Net-(RD-PadC)") (class "Default")
      (node (ref "RD") (pin "C") (pinfunction "C_C") (pintype "passive"))
      (node (ref "RRO") (pin "1") (pinfunction "1_1") (pintype "passive"))
    )
    (net (code "23") (name "Net-(RD1-PadC)") (class "Default")
      (node (ref "RD1") (pin "C") (pinfunction "C_C") (pintype "passive"))
      (node (ref "RRO1") (pin "1") (pinfunction "1_1") (pintype "passive"))
    )
    (net (code "24") (name "Net-(U1-I2C_ENB)") (class "Default")
      (node (ref "R3") (pin "2") (pinfunction "2_2") (pintype "passive"))
      (node (ref "U1") (pin "8") (pinfunction "I2C_ENB_8") (pintype "input"))
    )
    (net (code "25") (name "Net-(U2-I2C_ENB)") (class "Default")
      (node (ref "R5") (pin "2") (pinfunction "2_2") (pintype "passive"))
      (node (ref "U2") (pin "8") (pinfunction "I2C_ENB_8") (pintype "input"))
    )
    (net (code "26") (name "OSC_IN") (class "Default")
      (node (ref "OSCC1") (pin "1") (pinfunction "1_1") (pintype "passive"))
      (node (ref "U3") (pin "5") (pinfunction "PF0-OSC_IN_5") (pintype "bidirectional"))
      (node (ref "Y2") (pin "1") (pinfunction "1_1") (pintype "passive"))
    )
    (net (code "27") (name "OSC_OUT") (class "Default")
      (node (ref "OSCC2") (pin "1") (pinfunction "1_1") (pintype "passive"))
      (node (ref "U3") (pin "6") (pinfunction "PF1-OSC_OUT_6") (pintype "bidirectional"))
      (node (ref "Y2") (pin "3") (pinfunction "3_3") (pintype "passive"))
    )
    (net (code "28") (name "RESN") (class "Default")
      (node (ref "R7") (pin "1") (pinfunction "1_1") (pintype "passive"))
      (node (ref "SL1") (pin "2") (pinfunction "2_2") (pintype "passive"))
      (node (ref "U4") (pin "2") (pinfunction "RESN_2") (pintype "input"))
    )
    (net (code "29") (name "RX_S") (class "Default")
      (node (ref "U3") (pin "42") (pinfunction "PB6_42") (pintype "bidirectional"))
      (node (ref "U4") (pin "11") (pinfunction "RX/SCL_S_11") (pintype "bidirectional"))
    )
    (net (code "30") (name "RX_T") (class "Default")
      (node (ref "U3") (pin "21") (pinfunction "PB10_21") (pintype "bidirectional"))
      (node (ref "X1") (pin "3") (pinfunction "S_3") (pintype "passive"))
    )
    (net (code "31") (name "SCK") (class "Default")
      (node (ref "J1") (pin "5") (pinfunction "CLK(SCK)_5") (pintype "bidirectional"))
      (node (ref "U3") (pin "26") (pinfunction "PB13_26") (pintype "bidirectional"))
    )
    (net (code "32") (name "SCL_M") (class "Default")
      (node (ref "R15") (pin "1") (pinfunction "1_1") (pintype "passive"))
      (node (ref "U1") (pin "9") (pinfunction "SCL_M_9") (pintype "output"))
      (node (ref "U2") (pin "9") (pinfunction "SCL_M_9") (pintype "output"))
      (node (ref "U4") (pin "9") (pinfunction "SCL_M_9") (pintype "output"))
    )
    (net (code "33") (name "SDA_M") (class "Default")
      (node (ref "R16") (pin "1") (pinfunction "1_1") (pintype "passive"))
      (node (ref "U1") (pin "10") (pinfunction "SDA_M_10") (pintype "bidirectional"))
      (node (ref "U2") (pin "10") (pinfunction "SDA_M_10") (pintype "bidirectional"))
      (node (ref "U4") (pin "10") (pinfunction "SDA_M_10") (pintype "bidirectional"))
    )
    (net (code "34") (name "SLV1_R") (class "Default")
      (node (ref "R14") (pin "1") (pinfunction "1_1") (pintype "passive"))
      (node (ref "U1") (pin "2") (pinfunction "RESN_2") (pintype "input"))
      (node (ref "U4") (pin "1") (pinfunction "SLV1_RESN_1") (pintype "bidirectional"))
    )
    (net (code "35") (name "SLV2_R") (class "Default")
      (node (ref "R10") (pin "1") (pinfunction "1_1") (pintype "passive"))
      (node (ref "U2") (pin "2") (pinfunction "RESN_2") (pintype "input"))
      (node (ref "U4") (pin "20") (pinfunction "SLV2_RESN_20") (pintype "output"))
    )
    (net (code "36") (name "SWCLK") (class "Default")
      (node (ref "J3") (pin "3") (pinfunction "3_3") (pintype "passive"))
      (node (ref "U3") (pin "37") (pinfunction "PA14_37") (pintype "bidirectional"))
    )
    (net (code "37") (name "SWDIO") (class "Default")
      (node (ref "J3") (pin "2") (pinfunction "2_2") (pintype "passive"))
      (node (ref "U3") (pin "34") (pinfunction "PA13_34") (pintype "bidirectional"))
    )
    (net (code "38") (name "TX_S") (class "Default")
      (node (ref "U3") (pin "43") (pinfunction "PB7_43") (pintype "bidirectional"))
      (node (ref "U4") (pin "12") (pinfunction "TX/SDA_S_12") (pintype "bidirectional"))
    )
    (net (code "39") (name "TX_T") (class "Default")
      (node (ref "U3") (pin "22") (pinfunction "PB11_22") (pintype "bidirectional"))
      (node (ref "X1") (pin "2") (pinfunction "S_2") (pintype "passive"))
    )
    (net (code "40") (name "VDDA") (class "Default")
      (node (ref "L2") (pin "2") (pinfunction "2_2") (pintype "passive"))
      (node (ref "U3") (pin "9") (pinfunction "VDDA/VREF+_9") (pintype "power_in"))
      (node (ref "VDDA1") (pin "1") (pinfunction "1_1") (pintype "passive"))
      (node (ref "VDDA2") (pin "1") (pinfunction "1_1") (pintype "passive"))
    )
    (net (code "41") (name "VIN") (class "Default")
      (node (ref "RGD") (pin "A") (pinfunction "A_A") (pintype "passive"))
      (node (ref "SW1") (pin "2") (pinfunction "2_2") (pintype "passive"))
    )
    (net (code "42") (name "unconnected-(J1B-DAT1(RSV)-Pad8)") (class "Default")
      (node (ref "J1") (pin "8") (pinfunction "DAT1(RSV)_8") (pintype "bidirectional"))
    )
    (net (code "43") (name "unconnected-(J1B-DAT2(NC)-Pad1)") (class "Default")
      (node (ref "J1") (pin "1") (pinfunction "DAT2(NC)_1") (pintype "bidirectional"))
    )
    (net (code "44") (name "unconnected-(U1-CSN-Pad6)") (class "Default")
      (node (ref "U1") (pin "6") (pinfunction "CSN_6") (pintype "output"))
    )
    (net (code "45") (name "unconnected-(U1-INT-Pad13)") (class "Default")
      (node (ref "U1") (pin "13") (pinfunction "INT_13") (pintype "output"))
    )
    (net (code "46") (name "unconnected-(U1-LED_DRV-Pad15)") (class "Default")
      (node (ref "U1") (pin "15") (pinfunction "LED_DRV_15") (pintype "output"))
    )
    (net (code "47") (name "unconnected-(U1-LED_IND-Pad18)") (class "Default")
      (node (ref "U1") (pin "18") (pinfunction "LED_IND_18") (pintype "output"))
    )
    (net (code "48") (name "unconnected-(U1-MISO-Pad5)") (class "Default")
      (node (ref "U1") (pin "5") (pinfunction "MISO_5") (pintype "bidirectional"))
    )
    (net (code "49") (name "unconnected-(U1-MOSI-Pad4)") (class "Default")
      (node (ref "U1") (pin "4") (pinfunction "MOSI_4") (pintype "bidirectional"))
    )
    (net (code "50") (name "unconnected-(U1-RX{slash}SCL_S-Pad11)") (class "Default")
      (node (ref "U1") (pin "11") (pinfunction "RX/SCL_S_11") (pintype "bidirectional"))
    )
    (net (code "51") (name "unconnected-(U1-SCK-Pad3)") (class "Default")
      (node (ref "U1") (pin "3") (pinfunction "SCK_3") (pintype "output"))
    )
    (net (code "52") (name "unconnected-(U1-SLV1_RESN-Pad1)") (class "Default")
      (node (ref "U1") (pin "1") (pinfunction "SLV1_RESN_1") (pintype "bidirectional"))
    )
    (net (code "53") (name "unconnected-(U1-SLV2_RESN-Pad20)") (class "Default")
      (node (ref "U1") (pin "20") (pinfunction "SLV2_RESN_20") (pintype "output"))
    )
    (net (code "54") (name "unconnected-(U1-TX{slash}SDA_S-Pad12)") (class "Default")
      (node (ref "U1") (pin "12") (pinfunction "TX/SDA_S_12") (pintype "bidirectional"))
    )
    (net (code "55") (name "unconnected-(U2-CSN-Pad6)") (class "Default")
      (node (ref "U2") (pin "6") (pinfunction "CSN_6") (pintype "output"))
    )
    (net (code "56") (name "unconnected-(U2-INT-Pad13)") (class "Default")
      (node (ref "U2") (pin "13") (pinfunction "INT_13") (pintype "output"))
    )
    (net (code "57") (name "unconnected-(U2-LED_DRV-Pad15)") (class "Default")
      (node (ref "U2") (pin "15") (pinfunction "LED_DRV_15") (pintype "output"))
    )
    (net (code "58") (name "unconnected-(U2-LED_IND-Pad18)") (class "Default")
      (node (ref "U2") (pin "18") (pinfunction "LED_IND_18") (pintype "output"))
    )
    (net (code "59") (name "unconnected-(U2-MISO-Pad5)") (class "Default")
      (node (ref "U2") (pin "5") (pinfunction "MISO_5") (pintype "bidirectional"))
    )
    (net (code "60") (name "unconnected-(U2-MOSI-Pad4)") (class "Default")
      (node (ref "U2") (pin "4") (pinfunction "MOSI_4") (pintype "bidirectional"))
    )
    (net (code "61") (name "unconnected-(U2-RX{slash}SCL_S-Pad11)") (class "Default")
      (node (ref "U2") (pin "11") (pinfunction "RX/SCL_S_11") (pintype "bidirectional"))
    )
    (net (code "62") (name "unconnected-(U2-SCK-Pad3)") (class "Default")
      (node (ref "U2") (pin "3") (pinfunction "SCK_3") (pintype "output"))
    )
    (net (code "63") (name "unconnected-(U2-SLV1_RESN-Pad1)") (class "Default")
      (node (ref "U2") (pin "1") (pinfunction "SLV1_RESN_1") (pintype "bidirectional"))
    )
    (net (code "64") (name "unconnected-(U2-SLV2_RESN-Pad20)") (class "Default")
      (node (ref "U2") (pin "20") (pinfunction "SLV2_RESN_20") (pintype "output"))
    )
    (net (code "65") (name "unconnected-(U2-TX{slash}SDA_S-Pad12)") (class "Default")
      (node (ref "U2") (pin "12") (pinfunction "TX/SDA_S_12") (pintype "bidirectional"))
    )
    (net (code "66") (name "unconnected-(U3A-PA0-WKUP1-Pad10)") (class "Default")
      (node (ref "U3") (pin "10") (pinfunction "PA0-WKUP1_10") (pintype "bidirectional"))
    )
    (net (code "67") (name "unconnected-(U3A-PA1-Pad11)") (class "Default")
      (node (ref "U3") (pin "11") (pinfunction "PA1_11") (pintype "bidirectional"))
    )
    (net (code "68") (name "unconnected-(U3A-PA2-Pad12)") (class "Default")
      (node (ref "U3") (pin "12") (pinfunction "PA2_12") (pintype "bidirectional"))
    )
    (net (code "69") (name "unconnected-(U3A-PA3-Pad13)") (class "Default")
      (node (ref "U3") (pin "13") (pinfunction "PA3_13") (pintype "bidirectional"))
    )
    (net (code "70") (name "unconnected-(U3A-PA4-Pad14)") (class "Default")
      (node (ref "U3") (pin "14") (pinfunction "PA4_14") (pintype "bidirectional"))
    )
    (net (code "71") (name "unconnected-(U3A-PA5-Pad15)") (class "Default")
      (node (ref "U3") (pin "15") (pinfunction "PA5_15") (pintype "bidirectional"))
    )
    (net (code "72") (name "unconnected-(U3A-PA6-Pad16)") (class "Default")
      (node (ref "U3") (pin "16") (pinfunction "PA6_16") (pintype "bidirectional"))
    )
    (net (code "73") (name "unconnected-(U3A-PA7-Pad17)") (class "Default")
      (node (ref "U3") (pin "17") (pinfunction "PA7_17") (pintype "bidirectional"))
    )
    (net (code "74") (name "unconnected-(U3A-PA9-Pad30)") (class "Default")
      (node (ref "U3") (pin "30") (pinfunction "PA9_30") (pintype "bidirectional"))
    )
    (net (code "75") (name "unconnected-(U3A-PA10-Pad31)") (class "Default")
      (node (ref "U3") (pin "31") (pinfunction "PA10_31") (pintype "bidirectional"))
    )
    (net (code "76") (name "unconnected-(U3A-PA11-Pad32)") (class "Default")
      (node (ref "U3") (pin "32") (pinfunction "PA11_32") (pintype "bidirectional"))
    )
    (net (code "77") (name "unconnected-(U3A-PA12-Pad33)") (class "Default")
      (node (ref "U3") (pin "33") (pinfunction "PA12_33") (pintype "bidirectional"))
    )
    (net (code "78") (name "unconnected-(U3A-PB0-Pad18)") (class "Default")
      (node (ref "U3") (pin "18") (pinfunction "PB0_18") (pintype "bidirectional"))
    )
    (net (code "79") (name "unconnected-(U3A-PB1-Pad19)") (class "Default")
      (node (ref "U3") (pin "19") (pinfunction "PB1_19") (pintype "bidirectional"))
    )
    (net (code "80") (name "unconnected-(U3A-PB2-Pad20)") (class "Default")
      (node (ref "U3") (pin "20") (pinfunction "PB2_20") (pintype "bidirectional"))
    )
    (net (code "81") (name "unconnected-(U3A-PB4-Pad40)") (class "Default")
      (node (ref "U3") (pin "40") (pinfunction "PB4_40") (pintype "bidirectional"))
    )
    (net (code "82") (name "unconnected-(U3A-PB5-Pad41)") (class "Default")
      (node (ref "U3") (pin "41") (pinfunction "PB5_41") (pintype "bidirectional"))
    )
    (net (code "83") (name "unconnected-(U3A-PB8-Pad45)") (class "Default")
      (node (ref "U3") (pin "45") (pinfunction "PB8_45") (pintype "bidirectional"))
    )
    (net (code "84") (name "unconnected-(U3A-PB9-Pad46)") (class "Default")
      (node (ref "U3") (pin "46") (pinfunction "PB9_46") (pintype "bidirectional"))
    )
    (net (code "85") (name "unconnected-(U3A-PC13-WKUP2-Pad2)") (class "Default")
      (node (ref "U3") (pin "2") (pinfunction "PC13-WKUP2_2") (pintype "bidirectional"))
    )
    (net (code "86") (name "unconnected-(U3A-PC14-OSC32_IN-Pad3)") (class "Default")
      (node (ref "U3") (pin "3") (pinfunction "PC14-OSC32_IN_3") (pintype "bidirectional"))
    )
    (net (code "87") (name "unconnected-(U3A-PC15-OSC32_OUT-Pad4)") (class "Default")
      (node (ref "U3") (pin "4") (pinfunction "PC15-OSC32_OUT_4") (pintype "bidirectional"))
    )
    (net (code "88") (name "unconnected-(U4-LED_DRV-Pad15)") (class "Default")
      (node (ref "U4") (pin "15") (pinfunction "LED_DRV_15") (pintype "output"))
    )
  )
)
